# tube_driver_eagle.net
KiCad netlist of a schematic drawn in EAGLE
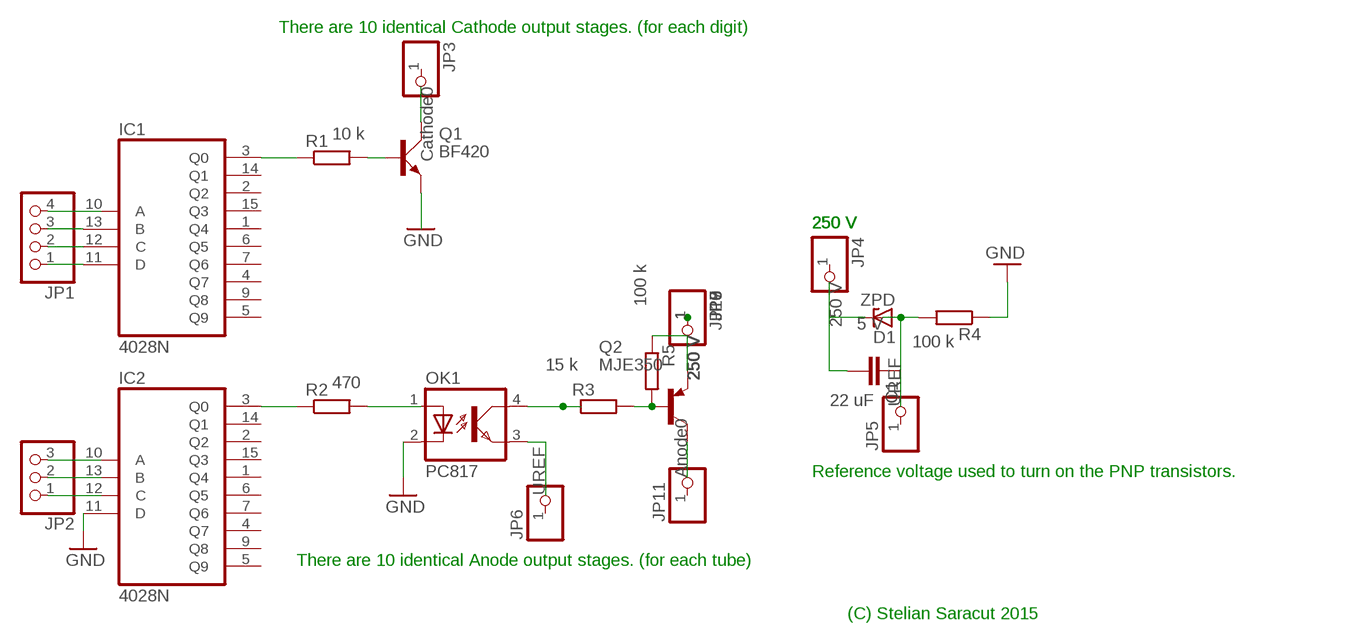
[diagram p0: schematic, sheet 1]

(export (version "E")
  (design (tool "Eeschema 10.0.6"))
  (components
    (comp (ref "C1")
      (value "C2,5-3")
      (footprint "eagle-import:C2.5-3")
      (fields (field (name "C1") "22 uF"))
      (libsource (lib "eagle-import") (part "C2,5-3"))
    )
    (comp (ref "D1")
      (value "ZPD")
      (footprint "eagle-import:DO35Z10")
      (fields (field (name "ZD1") "5 V"))
      (libsource (lib "eagle-import") (part "ZPD"))
    )
    (comp (ref "IC1")
      (value "4028N")
      (footprint "eagle-import:DIL16")
      (libsource (lib "eagle-import") (part "4028N"))
    )
    (comp (ref "IC2")
      (value "4028N")
      (footprint "eagle-import:DIL16")
      (libsource (lib "eagle-import") (part "4028N"))
    )
    (comp (ref "JP1")
      (value "PINHD-1X4")
      (footprint "eagle-import:1X04")
      (libsource (lib "eagle-import") (part "PINHD-1X4"))
    )
    (comp (ref "JP2")
      (value "PINHD-1X3")
      (footprint "eagle-import:1X03")
      (libsource (lib "eagle-import") (part "PINHD-1X3"))
    )
    (comp (ref "JP3")
      (value "PINHD-1X1")
      (footprint "eagle-import:1X01")
      (fields (field (name "P0") "Cathode0"))
      (libsource (lib "eagle-import") (part "PINHD-1X1"))
    )
    (comp (ref "JP4")
      (value "PINHD-1X1")
      (footprint "eagle-import:1X01")
      (fields (field (name "JP4") "250 V"))
      (libsource (lib "eagle-import") (part "PINHD-1X1"))
    )
    (comp (ref "JP5")
      (value "PINHD-1X1")
      (footprint "eagle-import:1X01")
      (fields (field (name "JP4") "UREF"))
      (libsource (lib "eagle-import") (part "PINHD-1X1"))
    )
    (comp (ref "JP6")
      (value "PINHD-1X1")
      (footprint "eagle-import:1X01")
      (fields (field (name "JP4") "UREF"))
      (libsource (lib "eagle-import") (part "PINHD-1X1"))
    )
    (comp (ref "JP7")
      (value "PINHD-1X1")
      (footprint "eagle-import:1X01")
      (fields (field (name "JP4") "250 V"))
      (libsource (lib "eagle-import") (part "PINHD-1X1"))
    )
    (comp (ref "JP8")
      (value "PINHD-1X1")
      (footprint "eagle-import:1X01")
      (fields (field (name "JP4") "250 V"))
      (libsource (lib "eagle-import") (part "PINHD-1X1"))
    )
    (comp (ref "JP9")
      (value "PINHD-1X1")
      (footprint "eagle-import:1X01")
      (fields (field (name "JP4") "250 V"))
      (libsource (lib "eagle-import") (part "PINHD-1X1"))
    )
    (comp (ref "JP10")
      (value "PINHD-1X1")
      (footprint "eagle-import:1X01")
      (fields (field (name "JP4") "250 V"))
      (libsource (lib "eagle-import") (part "PINHD-1X1"))
    )
    (comp (ref "JP11")
      (value "PINHD-1X1")
      (footprint "eagle-import:1X01")
      (fields (field (name "JP4") "Anode0"))
      (libsource (lib "eagle-import") (part "PINHD-1X1"))
    )
    (comp (ref "OK1")
      (value "PC817")
      (footprint "eagle-import:DIL04")
      (fields (field (name "MPN") "PC817X4J000F"))
      (libsource (lib "eagle-import") (part "PC817"))
    )
    (comp (ref "Q1")
      (value "BF420")
      (footprint "eagle-import:SOT54D")
      (libsource (lib "eagle-import") (part "BF420"))
    )
    (comp (ref "Q2")
      (value "MJE350")
      (footprint "eagle-import:TO126")
      (libsource (lib "eagle-import") (part "MJE350"))
    )
    (comp (ref "R1")
      (value "R-EU_0204/2V")
      (footprint "eagle-import:0204V")
      (fields (field (name "R1") "10 k"))
      (libsource (lib "eagle-import") (part "R-EU_0204/2V"))
    )
    (comp (ref "R2")
      (value "R-EU_0204/2V")
      (footprint "eagle-import:0204V")
      (fields (field (name "R2") "470"))
      (libsource (lib "eagle-import") (part "R-EU_0204/2V"))
    )
    (comp (ref "R3")
      (value "R-EU_0204/2V")
      (footprint "eagle-import:0204V")
      (fields (field (name "R1") "15 k"))
      (libsource (lib "eagle-import") (part "R-EU_0204/2V"))
    )
    (comp (ref "R4")
      (value "R-EU_0204/2V")
      (footprint "eagle-import:0204V")
      (fields (field (name "R1") "100 k"))
      (libsource (lib "eagle-import") (part "R-EU_0204/2V"))
    )
    (comp (ref "R5")
      (value "R-EU_0204/2V")
      (footprint "eagle-import:0204V")
      (fields (field (name "R1") "100 k"))
      (libsource (lib "eagle-import") (part "R-EU_0204/2V"))
    )
  )
  (nets
    (net (code "1") (name "GND") (class "Default")
      (node (ref "IC2") (pin "11") (pinfunction "D_11") (pintype "input"))
      (node (ref "OK1") (pin "2") (pinfunction "C_2") (pintype "passive"))
      (node (ref "Q1") (pin "E") (pinfunction "E_E") (pintype "passive"))
      (node (ref "R4") (pin "1") (pinfunction "1_1") (pintype "passive"))
    )
    (net (code "2") (name "Net-(C1-Pad1)") (class "Default")
      (node (ref "C1") (pin "1") (pinfunction "1_1") (pintype "passive"))
      (node (ref "D1") (pin "A") (pinfunction "A_A") (pintype "passive"))
      (node (ref "R4") (pin "2") (pinfunction "2_2") (pintype "passive"))
    )
    (net (code "3") (name "Net-(C1-Pad2)") (class "Default")
      (node (ref "C1") (pin "2") (pinfunction "2_2") (pintype "passive"))
      (node (ref "D1") (pin "C") (pinfunction "C_C") (pintype "passive"))
    )
    (net (code "4") (name "Net-(IC1A-B)") (class "Default")
      (node (ref "IC1") (pin "13") (pinfunction "B_13") (pintype "input"))
      (node (ref "JP1") (pin "3") (pinfunction "3_3") (pintype "passive"))
    )
    (net (code "5") (name "Net-(IC1A-C)") (class "Default")
      (node (ref "IC1") (pin "12") (pinfunction "C_12") (pintype "input"))
      (node (ref "JP1") (pin "2") (pinfunction "2_2") (pintype "passive"))
    )
    (net (code "6") (name "Net-(IC1A-D)") (class "Default")
      (node (ref "IC1") (pin "11") (pinfunction "D_11") (pintype "input"))
      (node (ref "JP1") (pin "1") (pinfunction "1_1") (pintype "passive"))
    )
    (net (code "7") (name "Net-(IC1A-Q0)") (class "Default")
      (node (ref "IC1") (pin "3") (pinfunction "Q0_3") (pintype "output"))
      (node (ref "R1") (pin "1") (pinfunction "1_1") (pintype "passive"))
    )
    (net (code "8") (name "Net-(IC2A-Q0)") (class "Default")
      (node (ref "IC2") (pin "3") (pinfunction "Q0_3") (pintype "output"))
      (node (ref "R2") (pin "1") (pinfunction "1_1") (pintype "passive"))
    )
    (net (code "9") (name "Net-(JP10-Pad1)") (class "Default")
      (node (ref "JP10") (pin "1") (pinfunction "1_1") (pintype "passive"))
      (node (ref "JP7") (pin "1") (pinfunction "1_1") (pintype "passive"))
      (node (ref "JP8") (pin "1") (pinfunction "1_1") (pintype "passive"))
      (node (ref "JP9") (pin "1") (pinfunction "1_1") (pintype "passive"))
    )
    (net (code "10") (name "Net-(OK1-COL)") (class "Default")
      (node (ref "OK1") (pin "4") (pinfunction "COL_4") (pintype "passive"))
      (node (ref "R3") (pin "1") (pinfunction "1_1") (pintype "passive"))
    )
    (net (code "11") (name "Net-(Q1-PadB)") (class "Default")
      (node (ref "Q1") (pin "B") (pinfunction "B_B") (pintype "passive"))
      (node (ref "R1") (pin "2") (pinfunction "2_2") (pintype "passive"))
    )
    (net (code "12") (name "Net-(Q2-B)") (class "Default")
      (node (ref "Q2") (pin "3") (pinfunction "B_3") (pintype "passive"))
      (node (ref "R3") (pin "2") (pinfunction "2_2") (pintype "passive"))
      (node (ref "R5") (pin "2") (pinfunction "2_2") (pintype "passive"))
    )
    (net (code "13") (name "Net-(Q2-E)") (class "Default")
      (node (ref "Q2") (pin "1") (pinfunction "E_1") (pintype "passive"))
      (node (ref "R5") (pin "1") (pinfunction "1_1") (pintype "passive"))
    )
    (net (code "14") (name "unconnected-(IC1A-A-Pad10)") (class "Default")
      (node (ref "IC1") (pin "10") (pinfunction "A_10") (pintype "input"))
    )
    (net (code "15") (name "unconnected-(IC1A-Q1-Pad14)") (class "Default")
      (node (ref "IC1") (pin "14") (pinfunction "Q1_14") (pintype "output"))
    )
    (net (code "16") (name "unconnected-(IC1A-Q2-Pad2)") (class "Default")
      (node (ref "IC1") (pin "2") (pinfunction "Q2_2") (pintype "output"))
    )
    (net (code "17") (name "unconnected-(IC1A-Q3-Pad15)") (class "Default")
      (node (ref "IC1") (pin "15") (pinfunction "Q3_15") (pintype "output"))
    )
    (net (code "18") (name "unconnected-(IC1A-Q4-Pad1)") (class "Default")
      (node (ref "IC1") (pin "1") (pinfunction "Q4_1") (pintype "output"))
    )
    (net (code "19") (name "unconnected-(IC1A-Q5-Pad6)") (class "Default")
      (node (ref "IC1") (pin "6") (pinfunction "Q5_6") (pintype "output"))
    )
    (net (code "20") (name "unconnected-(IC1A-Q6-Pad7)") (class "Default")
      (node (ref "IC1") (pin "7") (pinfunction "Q6_7") (pintype "output"))
    )
    (net (code "21") (name "unconnected-(IC1A-Q7-Pad4)") (class "Default")
      (node (ref "IC1") (pin "4") (pinfunction "Q7_4") (pintype "output"))
    )
    (net (code "22") (name "unconnected-(IC1A-Q8-Pad9)") (class "Default")
      (node (ref "IC1") (pin "9") (pinfunction "Q8_9") (pintype "output"))
    )
    (net (code "23") (name "unconnected-(IC1A-Q9-Pad5)") (class "Default")
      (node (ref "IC1") (pin "5") (pinfunction "Q9_5") (pintype "output"))
    )
    (net (code "24") (name "unconnected-(IC2A-A-Pad10)") (class "Default")
      (node (ref "IC2") (pin "10") (pinfunction "A_10") (pintype "input"))
    )
    (net (code "25") (name "unconnected-(IC2A-B-Pad13)") (class "Default")
      (node (ref "IC2") (pin "13") (pinfunction "B_13") (pintype "input"))
    )
    (net (code "26") (name "unconnected-(IC2A-C-Pad12)") (class "Default")
      (node (ref "IC2") (pin "12") (pinfunction "C_12") (pintype "input"))
    )
    (net (code "27") (name "unconnected-(IC2A-Q1-Pad14)") (class "Default")
      (node (ref "IC2") (pin "14") (pinfunction "Q1_14") (pintype "output"))
    )
    (net (code "28") (name "unconnected-(IC2A-Q2-Pad2)") (class "Default")
      (node (ref "IC2") (pin "2") (pinfunction "Q2_2") (pintype "output"))
    )
    (net (code "29") (name "unconnected-(IC2A-Q3-Pad15)") (class "Default")
      (node (ref "IC2") (pin "15") (pinfunction "Q3_15") (pintype "output"))
    )
    (net (code "30") (name "unconnected-(IC2A-Q4-Pad1)") (class "Default")
      (node (ref "IC2") (pin "1") (pinfunction "Q4_1") (pintype "output"))
    )
    (net (code "31") (name "unconnected-(IC2A-Q5-Pad6)") (class "Default")
      (node (ref "IC2") (pin "6") (pinfunction "Q5_6") (pintype "output"))
    )
    (net (code "32") (name "unconnected-(IC2A-Q6-Pad7)") (class "Default")
      (node (ref "IC2") (pin "7") (pinfunction "Q6_7") (pintype "output"))
    )
    (net (code "33") (name "unconnected-(IC2A-Q7-Pad4)") (class "Default")
      (node (ref "IC2") (pin "4") (pinfunction "Q7_4") (pintype "output"))
    )
    (net (code "34") (name "unconnected-(IC2A-Q8-Pad9)") (class "Default")
      (node (ref "IC2") (pin "9") (pinfunction "Q8_9") (pintype "output"))
    )
    (net (code "35") (name "unconnected-(IC2A-Q9-Pad5)") (class "Default")
      (node (ref "IC2") (pin "5") (pinfunction "Q9_5") (pintype "output"))
    )
    (net (code "36") (name "unconnected-(JP1-Pad4)") (class "Default")
      (node (ref "JP1") (pin "4") (pinfunction "4_4") (pintype "passive"))
    )
    (net (code "37") (name "unconnected-(JP2-Pad1)") (class "Default")
      (node (ref "JP2") (pin "1") (pinfunction "1_1") (pintype "passive"))
    )
    (net (code "38") (name "unconnected-(JP2-Pad2)") (class "Default")
      (node (ref "JP2") (pin "2") (pinfunction "2_2") (pintype "passive"))
    )
    (net (code "39") (name "unconnected-(JP2-Pad3)") (class "Default")
      (node (ref "JP2") (pin "3") (pinfunction "3_3") (pintype "passive"))
    )
    (net (code "40") (name "unconnected-(JP3-Pad1)") (class "Default")
      (node (ref "JP3") (pin "1") (pinfunction "1_1") (pintype "passive"))
    )
    (net (code "41") (name "unconnected-(JP4-Pad1)") (class "Default")
      (node (ref "JP4") (pin "1") (pinfunction "1_1") (pintype "passive"))
    )
    (net (code "42") (name "unconnected-(JP5-Pad1)") (class "Default")
      (node (ref "JP5") (pin "1") (pinfunction "1_1") (pintype "passive"))
    )
    (net (code "43") (name "unconnected-(JP6-Pad1)") (class "Default")
      (node (ref "JP6") (pin "1") (pinfunction "1_1") (pintype "passive"))
    )
    (net (code "44") (name "unconnected-(JP11-Pad1)") (class "Default")
      (node (ref "JP11") (pin "1") (pinfunction "1_1") (pintype "passive"))
    )
    (net (code "45") (name "unconnected-(OK1-A-Pad1)") (class "Default")
      (node (ref "OK1") (pin "1") (pinfunction "A_1") (pintype "passive"))
    )
    (net (code "46") (name "unconnected-(OK1-EMIT-Pad3)") (class "Default")
      (node (ref "OK1") (pin "3") (pinfunction "EMIT_3") (pintype "passive"))
    )
    (net (code "47") (name "unconnected-(Q1-PadC)") (class "Default")
      (node (ref "Q1") (pin "C") (pinfunction "C_C") (pintype "passive"))
    )
    (net (code "48") (name "unconnected-(Q2-C-Pad2)") (class "Default")
      (node (ref "Q2") (pin "2") (pinfunction "C_2") (pintype "passive"))
    )
    (net (code "49") (name "unconnected-(R2-Pad2)") (class "Default")
      (node (ref "R2") (pin "2") (pinfunction "2_2") (pintype "passive"))
    )
  )
)
